# Adafruit_QT_Py_ESP32_Pico.net
KiCad netlist of a schematic drawn in EAGLE
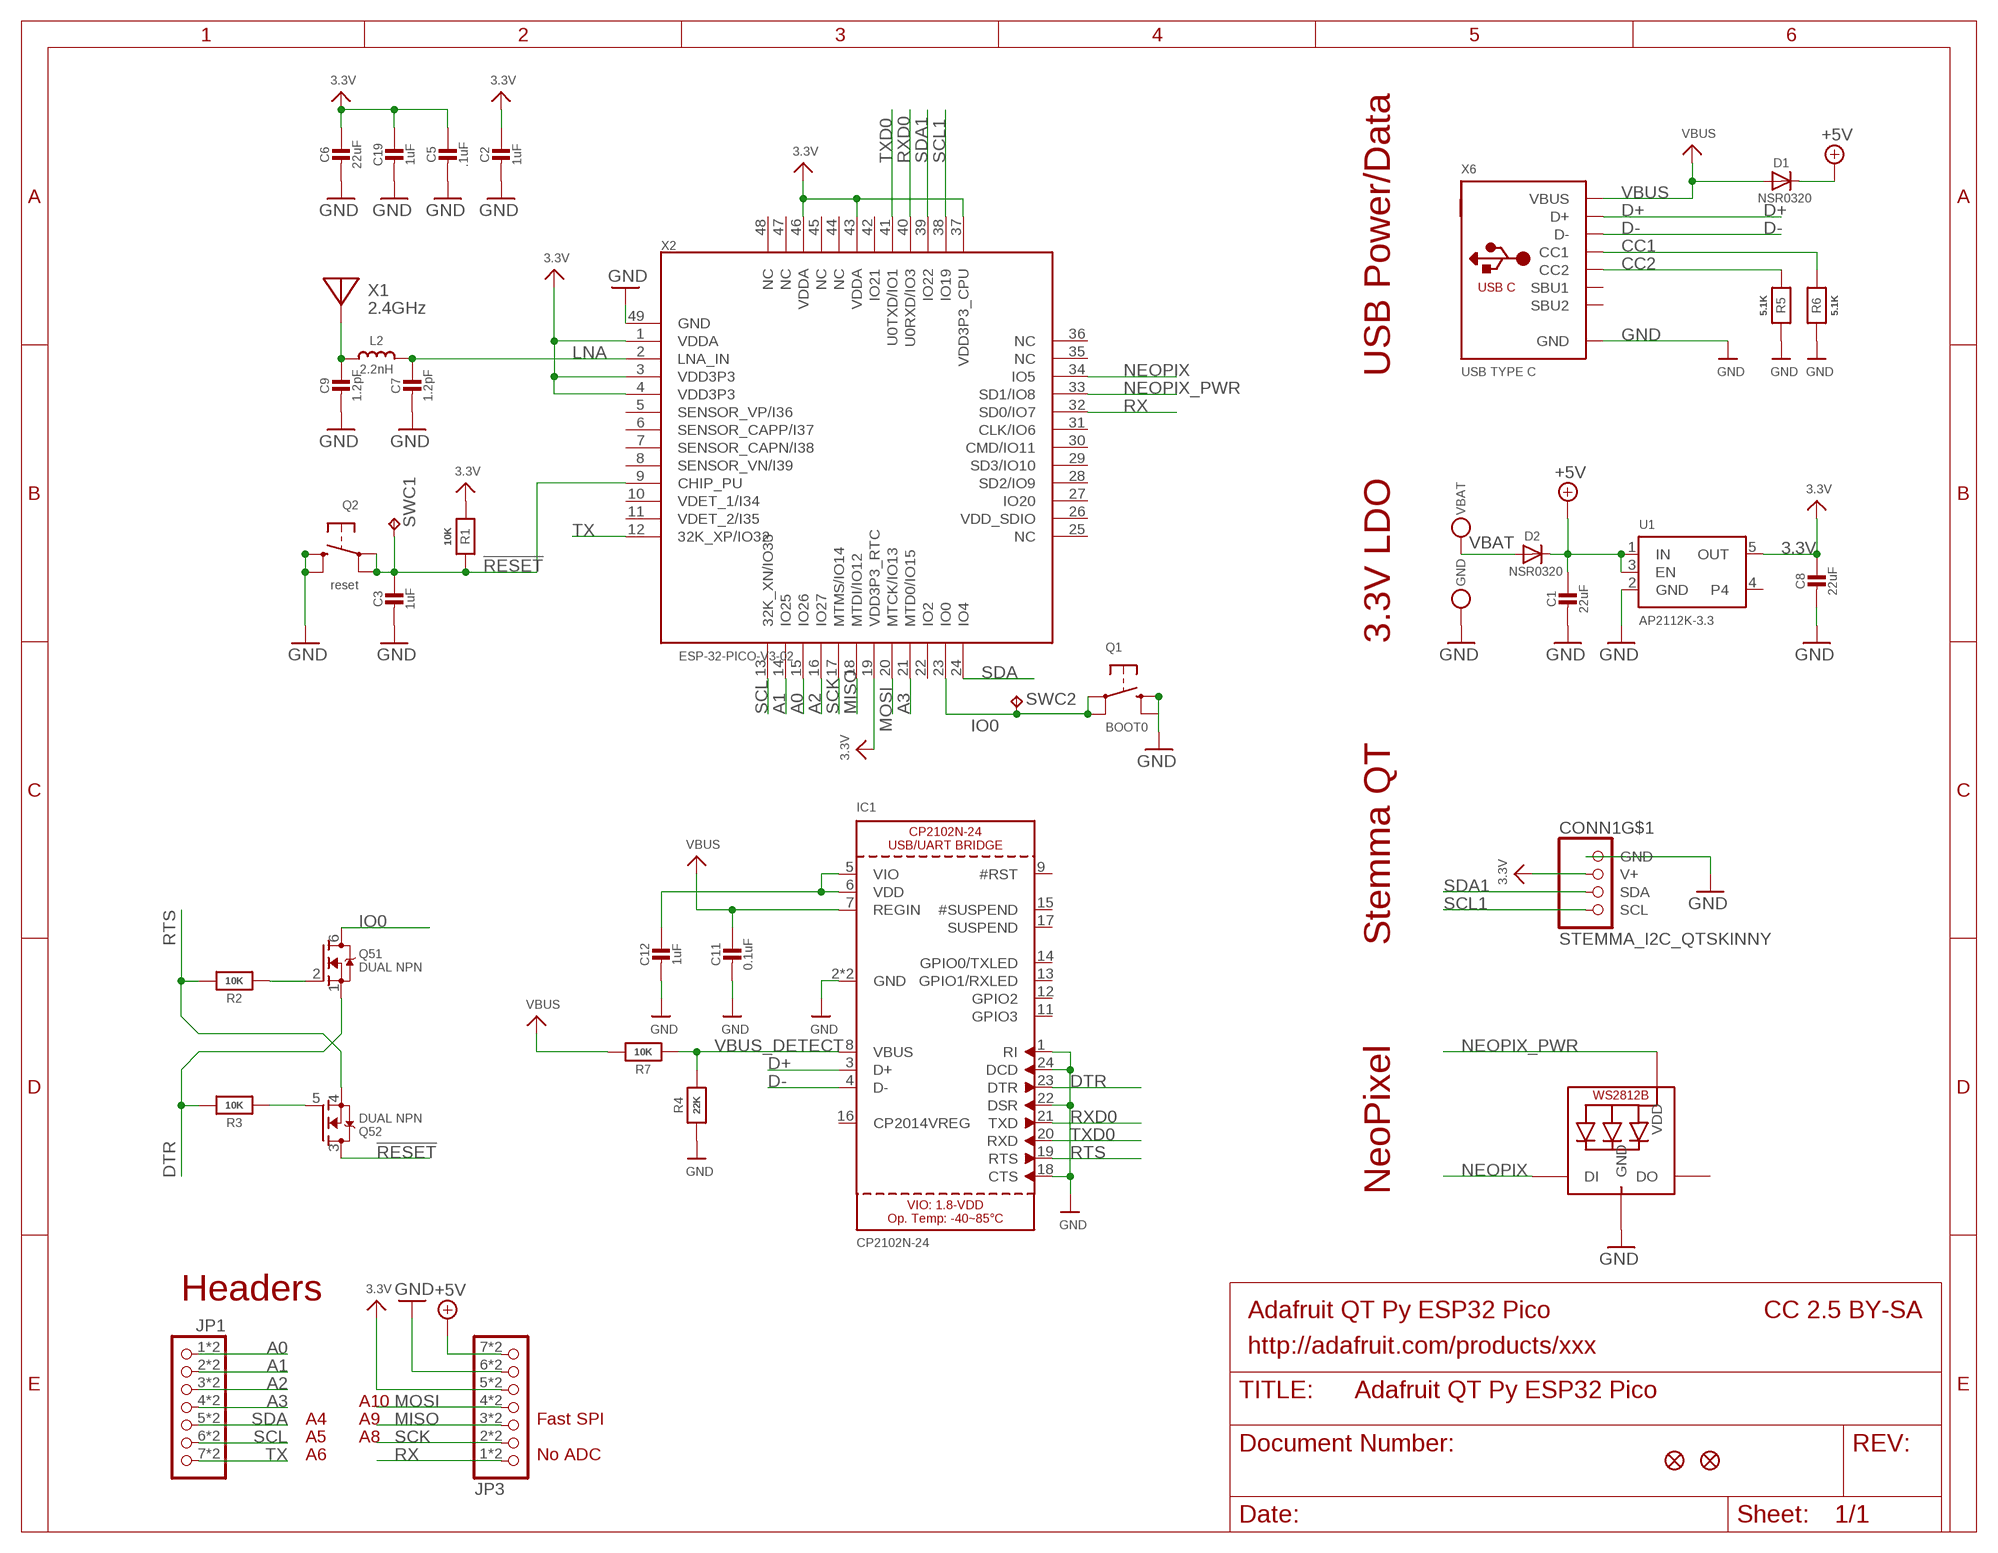
[diagram p0: schematic, sheet 1]

(export (version "E")
  (design (tool "Eeschema 10.0.6"))
  (components
    (comp (ref "C1")
      (value "22uF")
      (footprint "eagle-import:0805-NO")
      (libsource (lib "eagle-import") (part "CAP_CERAMIC0805-NOOUTLINE"))
    )
    (comp (ref "C2")
      (value "1uF")
      (footprint "eagle-import:_0402NO")
      (libsource (lib "eagle-import") (part "CAP_CERAMIC_0402NO"))
    )
    (comp (ref "C3")
      (value "1uF")
      (footprint "eagle-import:_0402NO")
      (libsource (lib "eagle-import") (part "CAP_CERAMIC_0402NO"))
    )
    (comp (ref "C5")
      (value ".1uF")
      (footprint "eagle-import:_0402NO")
      (libsource (lib "eagle-import") (part "CAP_CERAMIC_0402NO"))
    )
    (comp (ref "C6")
      (value "22uF")
      (footprint "eagle-import:0805-NO")
      (libsource (lib "eagle-import") (part "CAP_CERAMIC0805-NOOUTLINE"))
    )
    (comp (ref "C7")
      (value "1.2pF")
      (footprint "eagle-import:_0402NO")
      (libsource (lib "eagle-import") (part "CAP_CERAMIC_0402NO"))
    )
    (comp (ref "C8")
      (value "22uF")
      (footprint "eagle-import:0805-NO")
      (libsource (lib "eagle-import") (part "CAP_CERAMIC0805-NOOUTLINE"))
    )
    (comp (ref "C9")
      (value "1.2pF")
      (footprint "eagle-import:_0402NO")
      (libsource (lib "eagle-import") (part "CAP_CERAMIC_0402NO"))
    )
    (comp (ref "C11")
      (value "0.1uF")
      (footprint "eagle-import:_0402NO")
      (libsource (lib "eagle-import") (part "CAP_CERAMIC_0402NO"))
    )
    (comp (ref "C12")
      (value "1uF")
      (footprint "eagle-import:_0402NO")
      (libsource (lib "eagle-import") (part "CAP_CERAMIC_0402NO"))
    )
    (comp (ref "C19")
      (value "1uF")
      (footprint "eagle-import:0603-NO_WIDE")
      (libsource (lib "eagle-import") (part "CAP_CERAMIC_0603WIDE"))
    )
    (comp (ref "CONN1")
      (value "STEMMA_I2C_QTSKINNY")
      (footprint "eagle-import:JST_SH4_SKINNY")
      (libsource (lib "eagle-import") (part "STEMMA_I2C_QTSKINNY"))
    )
    (comp (ref "D1")
      (value "NSR0320")
      (footprint "eagle-import:SOD-323_MINI")
      (libsource (lib "eagle-import") (part "DIODE_SOD323MINI"))
    )
    (comp (ref "D2")
      (value "NSR0320")
      (footprint "eagle-import:SOD-323_MINI")
      (libsource (lib "eagle-import") (part "DIODE_SOD323MINI"))
    )
    (comp (ref "GND")
      (value "TESTPOINT_MINUS")
      (footprint "eagle-import:TESTPOINT_MINUS_1X3MM")
      (libsource (lib "eagle-import") (part "TESTPOINT_MINUS"))
    )
    (comp (ref "IC1")
      (value "CP2102N-24")
      (footprint "eagle-import:QFN24_4MM_SMSC")
      (libsource (lib "eagle-import") (part "CP2102N-24"))
    )
    (comp (ref "JP1")
      (value "HEADER-1X7_CASTEL")
      (footprint "eagle-import:1X07_CASTEL")
      (libsource (lib "eagle-import") (part "HEADER-1X7_CASTEL"))
    )
    (comp (ref "JP3")
      (value "HEADER-1X7_CASTEL")
      (footprint "eagle-import:1X07_CASTEL")
      (libsource (lib "eagle-import") (part "HEADER-1X7_CASTEL"))
    )
    (comp (ref "L2")
      (value "2.2nH")
      (footprint "eagle-import:_0402")
      (libsource (lib "eagle-import") (part "INDUCTOR_0402"))
    )
    (comp (ref "LED1")
      (value "WS2812B_SK6805_1515")
      (footprint "eagle-import:SK6805_1515")
      (libsource (lib "eagle-import") (part "WS2812B_SK6805_1515"))
    )
    (comp (ref "Q1")
      (value "BOOT0")
      (footprint "eagle-import:BTN_KMR2_4.6X2.8")
      (libsource (lib "eagle-import") (part "SWITCH_TACT_SMT4.6X2.8"))
    )
    (comp (ref "Q2")
      (value "reset")
      (footprint "eagle-import:BTN_KMR2_4.6X2.8")
      (libsource (lib "eagle-import") (part "SWITCH_TACT_SMT4.6X2.8"))
    )
    (comp (ref "Q5")
      (value "DUAL NPN")
      (footprint "eagle-import:SOT363")
      (libsource (lib "eagle-import") (part "MOSFET-N_DUAL"))
    )
    (comp (ref "R1")
      (value "10K")
      (footprint "eagle-import:_0402NO")
      (libsource (lib "eagle-import") (part "RESISTOR_0402NO"))
    )
    (comp (ref "R2")
      (value "10K")
      (footprint "eagle-import:_0402NO")
      (libsource (lib "eagle-import") (part "RESISTOR_0402NO"))
    )
    (comp (ref "R3")
      (value "10K")
      (footprint "eagle-import:_0402NO")
      (libsource (lib "eagle-import") (part "RESISTOR_0402NO"))
    )
    (comp (ref "R4")
      (value "22K")
      (footprint "eagle-import:_0402NO")
      (libsource (lib "eagle-import") (part "RESISTOR_0402NO"))
    )
    (comp (ref "R5")
      (value "5.1K")
      (footprint "eagle-import:_0402NO")
      (libsource (lib "eagle-import") (part "RESISTOR_0402NO"))
    )
    (comp (ref "R6")
      (value "5.1K")
      (footprint "eagle-import:_0402NO")
      (libsource (lib "eagle-import") (part "RESISTOR_0402NO"))
    )
    (comp (ref "R7")
      (value "10K")
      (footprint "eagle-import:_0402NO")
      (libsource (lib "eagle-import") (part "RESISTOR_0402NO"))
    )
    (comp (ref "SWC1")
      (value "TPB1,27")
      (footprint "eagle-import:B1,27")
      (libsource (lib "eagle-import") (part "TPB1,27"))
    )
    (comp (ref "SWC2")
      (value "TPB1,27")
      (footprint "eagle-import:B1,27")
      (libsource (lib "eagle-import") (part "TPB1,27"))
    )
    (comp (ref "U$6")
      (value "FIDUCIAL_1MM")
      (footprint "eagle-import:FIDUCIAL_1MM")
      (libsource (lib "eagle-import") (part "FIDUCIAL_1MM"))
    )
    (comp (ref "U$8")
      (value "FIDUCIAL_1MM")
      (footprint "eagle-import:FIDUCIAL_1MM")
      (libsource (lib "eagle-import") (part "FIDUCIAL_1MM"))
    )
    (comp (ref "U1")
      (value "AP2112K-3.3")
      (footprint "eagle-import:SOT23-5")
      (libsource (lib "eagle-import") (part "VREG_SOT23-5"))
    )
    (comp (ref "VBAT")
      (value "TESTPOINT_PLUS13")
      (footprint "eagle-import:TESTPOINT_PLUS_1X3MM")
      (libsource (lib "eagle-import") (part "TESTPOINT_PLUS13"))
    )
    (comp (ref "X1")
      (value "2.4GHz")
      (footprint "eagle-import:ANT_2450AT18B100")
      (libsource (lib "eagle-import") (part "ANTENNA_JOHANSON_2450AT18B100"))
    )
    (comp (ref "X2")
      (value "ESP-32-PICO-V3-02")
      (footprint "eagle-import:QFN48_7X7")
      (libsource (lib "eagle-import") (part "ESP-32-PICO-V3-02"))
    )
    (comp (ref "X6")
      (value "USB TYPE C")
      (footprint "eagle-import:USB_C_CUSB31-CFM2AX-01-X")
      (libsource (lib "eagle-import") (part "USB_C"))
    )
  )
  (nets
    (net (code "1") (name "+5V") (class "Default")
      (node (ref "C1") (pin "1") (pinfunction "1_1") (pintype "passive"))
      (node (ref "D1") (pin "C") (pinfunction "C_C") (pintype "passive"))
      (node (ref "D2") (pin "C") (pinfunction "C_C") (pintype "passive"))
      (node (ref "JP3") (pin "7") (pinfunction "7_7") (pintype "passive"))
      (node (ref "JP3") (pin "7C") (pinfunction "7_7C") (pintype "passive"))
      (node (ref "U1") (pin "1") (pinfunction "IN_1") (pintype "power_in"))
      (node (ref "U1") (pin "3") (pinfunction "EN_3") (pintype "input"))
    )
    (net (code "2") (name "/A0") (class "Default")
      (node (ref "JP1") (pin "1") (pinfunction "1_1") (pintype "passive"))
      (node (ref "JP1") (pin "1C") (pinfunction "1_1C") (pintype "passive"))
      (node (ref "X2") (pin "15") (pinfunction "IO26_15") (pintype "bidirectional"))
    )
    (net (code "3") (name "/A1") (class "Default")
      (node (ref "JP1") (pin "2") (pinfunction "2_2") (pintype "passive"))
      (node (ref "JP1") (pin "2C") (pinfunction "2_2C") (pintype "passive"))
      (node (ref "X2") (pin "14") (pinfunction "IO25_14") (pintype "bidirectional"))
    )
    (net (code "4") (name "/A2") (class "Default")
      (node (ref "JP1") (pin "3") (pinfunction "3_3") (pintype "passive"))
      (node (ref "JP1") (pin "3C") (pinfunction "3_3C") (pintype "passive"))
      (node (ref "X2") (pin "16") (pinfunction "IO27_16") (pintype "bidirectional"))
    )
    (net (code "5") (name "/A3") (class "Default")
      (node (ref "JP1") (pin "4") (pinfunction "4_4") (pintype "passive"))
      (node (ref "JP1") (pin "4C") (pinfunction "4_4C") (pintype "passive"))
      (node (ref "X2") (pin "21") (pinfunction "MTD0/IO15_21") (pintype "bidirectional"))
    )
    (net (code "6") (name "/CC1") (class "Default")
      (node (ref "R6") (pin "2") (pinfunction "2_2") (pintype "passive"))
      (node (ref "X6") (pin "A5") (pinfunction "CC1_A5") (pintype "bidirectional"))
    )
    (net (code "7") (name "/CC2") (class "Default")
      (node (ref "R5") (pin "2") (pinfunction "2_2") (pintype "passive"))
      (node (ref "X6") (pin "B5") (pinfunction "CC2_B5") (pintype "bidirectional"))
    )
    (net (code "8") (name "/D+") (class "Default")
      (node (ref "IC1") (pin "3") (pinfunction "D+_3") (pintype "bidirectional"))
      (node (ref "X6") (pin "A6") (pinfunction "D+_A6") (pintype "bidirectional"))
      (node (ref "X6") (pin "B6") (pinfunction "D+_B6") (pintype "bidirectional"))
    )
    (net (code "9") (name "/D-") (class "Default")
      (node (ref "IC1") (pin "4") (pinfunction "D-_4") (pintype "bidirectional"))
      (node (ref "X6") (pin "A7") (pinfunction "D-_A7") (pintype "bidirectional"))
      (node (ref "X6") (pin "B7") (pinfunction "D-_B7") (pintype "bidirectional"))
    )
    (net (code "10") (name "/DTR") (class "Default")
      (node (ref "IC1") (pin "23") (pinfunction "DTR_23") (pintype "output"))
      (node (ref "Q5") (pin "1") (pinfunction "S_1") (pintype "bidirectional"))
      (node (ref "R3") (pin "2") (pinfunction "2_2") (pintype "passive"))
    )
    (net (code "11") (name "/IO0") (class "Default")
      (node (ref "Q1") (pin "A") (pinfunction "P_A") (pintype "passive"))
      (node (ref "Q1") (pin "A'") (pinfunction "P1_A'") (pintype "passive"))
      (node (ref "Q5") (pin "6") (pinfunction "D_6") (pintype "bidirectional"))
      (node (ref "SWC2") (pin "TP") (pinfunction "TP_TP") (pintype "input"))
      (node (ref "X2") (pin "23") (pinfunction "IO0_23") (pintype "bidirectional"))
    )
    (net (code "12") (name "/LNA") (class "Default")
      (node (ref "C7") (pin "1") (pinfunction "1_1") (pintype "passive"))
      (node (ref "L2") (pin "2") (pinfunction "2_2") (pintype "passive"))
      (node (ref "X2") (pin "2") (pinfunction "LNA_IN_2") (pintype "bidirectional"))
    )
    (net (code "13") (name "/MISO") (class "Default")
      (node (ref "JP3") (pin "3") (pinfunction "3_3") (pintype "passive"))
      (node (ref "JP3") (pin "3C") (pinfunction "3_3C") (pintype "passive"))
      (node (ref "X2") (pin "18") (pinfunction "MTDI/IO12_18") (pintype "bidirectional"))
    )
    (net (code "14") (name "/MOSI") (class "Default")
      (node (ref "JP3") (pin "4") (pinfunction "4_4") (pintype "passive"))
      (node (ref "JP3") (pin "4C") (pinfunction "4_4C") (pintype "passive"))
      (node (ref "X2") (pin "20") (pinfunction "MTCK/IO13_20") (pintype "bidirectional"))
    )
    (net (code "15") (name "/NEOPIX") (class "Default")
      (node (ref "LED1") (pin "1") (pinfunction "DI_1") (pintype "input"))
      (node (ref "X2") (pin "34") (pinfunction "IO5_34") (pintype "bidirectional"))
    )
    (net (code "16") (name "/NEOPIX_PWR") (class "Default")
      (node (ref "LED1") (pin "2") (pinfunction "VDD_2") (pintype "power_in"))
      (node (ref "X2") (pin "33") (pinfunction "SD1/IO8_33") (pintype "bidirectional"))
    )
    (net (code "17") (name "/RTS") (class "Default")
      (node (ref "IC1") (pin "19") (pinfunction "RTS_19") (pintype "output"))
      (node (ref "Q5") (pin "4") (pinfunction "S_4") (pintype "bidirectional"))
      (node (ref "R2") (pin "2") (pinfunction "2_2") (pintype "passive"))
    )
    (net (code "18") (name "/RX") (class "Default")
      (node (ref "JP3") (pin "1") (pinfunction "1_1") (pintype "passive"))
      (node (ref "JP3") (pin "1C") (pinfunction "1_1C") (pintype "passive"))
      (node (ref "X2") (pin "32") (pinfunction "SD0/IO7_32") (pintype "bidirectional"))
    )
    (net (code "19") (name "/RXD0") (class "Default")
      (node (ref "IC1") (pin "21") (pinfunction "TXD_21") (pintype "output"))
      (node (ref "X2") (pin "40") (pinfunction "U0RXD/IO3_40") (pintype "bidirectional"))
    )
    (net (code "20") (name "/SCK") (class "Default")
      (node (ref "JP3") (pin "2") (pinfunction "2_2") (pintype "passive"))
      (node (ref "JP3") (pin "2C") (pinfunction "2_2C") (pintype "passive"))
      (node (ref "X2") (pin "17") (pinfunction "MTMS/IO14_17") (pintype "bidirectional"))
    )
    (net (code "21") (name "/SCL") (class "Default")
      (node (ref "JP1") (pin "6") (pinfunction "6_6") (pintype "passive"))
      (node (ref "JP1") (pin "6C") (pinfunction "6_6C") (pintype "passive"))
      (node (ref "X2") (pin "13") (pinfunction "32K_XN/IO33_13") (pintype "bidirectional"))
    )
    (net (code "22") (name "/SCL1") (class "Default")
      (node (ref "CONN1") (pin "4") (pinfunction "SCL_4") (pintype "passive"))
      (node (ref "X2") (pin "38") (pinfunction "IO19_38") (pintype "bidirectional"))
    )
    (net (code "23") (name "/SDA") (class "Default")
      (node (ref "JP1") (pin "5") (pinfunction "5_5") (pintype "passive"))
      (node (ref "JP1") (pin "5C") (pinfunction "5_5C") (pintype "passive"))
      (node (ref "X2") (pin "24") (pinfunction "IO4_24") (pintype "bidirectional"))
    )
    (net (code "24") (name "/SDA1") (class "Default")
      (node (ref "CONN1") (pin "3") (pinfunction "SDA_3") (pintype "passive"))
      (node (ref "X2") (pin "39") (pinfunction "IO22_39") (pintype "bidirectional"))
    )
    (net (code "25") (name "/TX") (class "Default")
      (node (ref "JP1") (pin "7") (pinfunction "7_7") (pintype "passive"))
      (node (ref "JP1") (pin "7C") (pinfunction "7_7C") (pintype "passive"))
      (node (ref "X2") (pin "12") (pinfunction "32K_XP/IO32_12") (pintype "bidirectional"))
    )
    (net (code "26") (name "/TXD0") (class "Default")
      (node (ref "IC1") (pin "20") (pinfunction "RXD_20") (pintype "input"))
      (node (ref "X2") (pin "41") (pinfunction "U0TXD/IO1_41") (pintype "bidirectional"))
    )
    (net (code "27") (name "/VBAT") (class "Default")
      (node (ref "D2") (pin "A") (pinfunction "A_A") (pintype "passive"))
      (node (ref "VBAT") (pin "P$1") (pinfunction "P$1_P$1") (pintype "bidirectional"))
    )
    (net (code "28") (name "/VBUS_DETECT") (class "Default")
      (node (ref "IC1") (pin "8") (pinfunction "VBUS_8") (pintype "power_in"))
      (node (ref "R4") (pin "2") (pinfunction "2_2") (pintype "passive"))
      (node (ref "R7") (pin "1") (pinfunction "1_1") (pintype "passive"))
    )
    (net (code "29") (name "/~{RESET}") (class "Default")
      (node (ref "C3") (pin "1") (pinfunction "1_1") (pintype "passive"))
      (node (ref "Q2") (pin "A") (pinfunction "P_A") (pintype "passive"))
      (node (ref "Q2") (pin "A'") (pinfunction "P1_A'") (pintype "passive"))
      (node (ref "Q5") (pin "3") (pinfunction "D_3") (pintype "bidirectional"))
      (node (ref "R1") (pin "2") (pinfunction "2_2") (pintype "passive"))
      (node (ref "SWC1") (pin "TP") (pinfunction "TP_TP") (pintype "input"))
      (node (ref "X2") (pin "9") (pinfunction "CHIP_PU_9") (pintype "input"))
    )
    (net (code "30") (name "3.3V") (class "Default")
      (node (ref "C19") (pin "1") (pinfunction "1_1") (pintype "passive"))
      (node (ref "C2") (pin "1") (pinfunction "1_1") (pintype "passive"))
      (node (ref "C5") (pin "1") (pinfunction "1_1") (pintype "passive"))
      (node (ref "C6") (pin "1") (pinfunction "1_1") (pintype "passive"))
      (node (ref "C8") (pin "1") (pinfunction "1_1") (pintype "passive"))
      (node (ref "CONN1") (pin "2") (pinfunction "V+_2") (pintype "passive"))
      (node (ref "JP3") (pin "5") (pinfunction "5_5") (pintype "passive"))
      (node (ref "JP3") (pin "5C") (pinfunction "5_5C") (pintype "passive"))
      (node (ref "R1") (pin "1") (pinfunction "1_1") (pintype "passive"))
      (node (ref "U1") (pin "5") (pinfunction "OUT_5") (pintype "power_in"))
      (node (ref "X2") (pin "1") (pinfunction "VDDA_1") (pintype "power_in"))
      (node (ref "X2") (pin "19") (pinfunction "VDD3P3_RTC_19") (pintype "power_in"))
      (node (ref "X2") (pin "3") (pinfunction "VDD3P3_3") (pintype "power_in"))
      (node (ref "X2") (pin "37") (pinfunction "VDD3P3_CPU_37") (pintype "power_in"))
      (node (ref "X2") (pin "4") (pinfunction "VDD3P3_4") (pintype "power_in"))
      (node (ref "X2") (pin "43") (pinfunction "VDDA_43") (pintype "power_in"))
      (node (ref "X2") (pin "46") (pinfunction "VDDA_46") (pintype "power_in"))
    )
    (net (code "31") (name "GND") (class "Default")
      (node (ref "C1") (pin "2") (pinfunction "2_2") (pintype "passive"))
      (node (ref "C11") (pin "2") (pinfunction "2_2") (pintype "passive"))
      (node (ref "C12") (pin "2") (pinfunction "2_2") (pintype "passive"))
      (node (ref "C19") (pin "2") (pinfunction "2_2") (pintype "passive"))
      (node (ref "C2") (pin "2") (pinfunction "2_2") (pintype "passive"))
      (node (ref "C3") (pin "2") (pinfunction "2_2") (pintype "passive"))
      (node (ref "C5") (pin "2") (pinfunction "2_2") (pintype "passive"))
      (node (ref "C6") (pin "2") (pinfunction "2_2") (pintype "passive"))
      (node (ref "C7") (pin "2") (pinfunction "2_2") (pintype "passive"))
      (node (ref "C8") (pin "2") (pinfunction "2_2") (pintype "passive"))
      (node (ref "C9") (pin "2") (pinfunction "2_2") (pintype "passive"))
      (node (ref "CONN1") (pin "1") (pinfunction "GND_1") (pintype "passive"))
      (node (ref "GND") (pin "P$1") (pinfunction "P$1_P$1") (pintype "bidirectional"))
      (node (ref "IC1") (pin "1") (pinfunction "RI_1") (pintype "input"))
      (node (ref "IC1") (pin "18") (pinfunction "CTS_18") (pintype "input"))
      (node (ref "IC1") (pin "2") (pinfunction "GND_2") (pintype "power_in"))
      (node (ref "IC1") (pin "22") (pinfunction "DSR_22") (pintype "input"))
      (node (ref "IC1") (pin "24") (pinfunction "DCD_24") (pintype "input"))
      (node (ref "IC1") (pin "THERM") (pinfunction "GND_THERM") (pintype "power_in"))
      (node (ref "JP3") (pin "6") (pinfunction "6_6") (pintype "passive"))
      (node (ref "JP3") (pin "6C") (pinfunction "6_6C") (pintype "passive"))
      (node (ref "LED1") (pin "4") (pinfunction "GND_4") (pintype "power_in"))
      (node (ref "Q1") (pin "B") (pinfunction "S_B") (pintype "passive"))
      (node (ref "Q1") (pin "B'") (pinfunction "S1_B'") (pintype "passive"))
      (node (ref "Q2") (pin "B") (pinfunction "S_B") (pintype "passive"))
      (node (ref "Q2") (pin "B'") (pinfunction "S1_B'") (pintype "passive"))
      (node (ref "R4") (pin "1") (pinfunction "1_1") (pintype "passive"))
      (node (ref "R5") (pin "1") (pinfunction "1_1") (pintype "passive"))
      (node (ref "R6") (pin "1") (pinfunction "1_1") (pintype "passive"))
      (node (ref "U1") (pin "2") (pinfunction "GND_2") (pintype "power_in"))
      (node (ref "X2") (pin "49") (pinfunction "GND_49") (pintype "power_in"))
      (node (ref "X6") (pin "A1B12") (pinfunction "GND_A1B12") (pintype "power_in"))
      (node (ref "X6") (pin "B1A12") (pinfunction "GND_B1A12") (pintype "power_in"))
    )
    (net (code "32") (name "Net-(IC1-VDD)") (class "Default")
      (node (ref "C12") (pin "1") (pinfunction "1_1") (pintype "passive"))
      (node (ref "IC1") (pin "5") (pinfunction "VIO_5") (pintype "power_in"))
      (node (ref "IC1") (pin "6") (pinfunction "VDD_6") (pintype "power_in"))
    )
    (net (code "33") (name "Net-(Q5A-G)") (class "Default")
      (node (ref "Q5") (pin "2") (pinfunction "G_2") (pintype "bidirectional"))
      (node (ref "R2") (pin "1") (pinfunction "1_1") (pintype "passive"))
    )
    (net (code "34") (name "Net-(Q5B-G)") (class "Default")
      (node (ref "Q5") (pin "5") (pinfunction "G_5") (pintype "bidirectional"))
      (node (ref "R3") (pin "1") (pinfunction "1_1") (pintype "passive"))
    )
    (net (code "35") (name "Net-(X1-P$1)") (class "Default")
      (node (ref "C9") (pin "1") (pinfunction "1_1") (pintype "passive"))
      (node (ref "L2") (pin "1") (pinfunction "1_1") (pintype "passive"))
      (node (ref "X1") (pin "FP") (pinfunction "P$1_FP") (pintype "passive"))
    )
    (net (code "36") (name "VBUS") (class "Default")
      (node (ref "C11") (pin "1") (pinfunction "1_1") (pintype "passive"))
      (node (ref "D1") (pin "A") (pinfunction "A_A") (pintype "passive"))
      (node (ref "IC1") (pin "7") (pinfunction "REGIN_7") (pintype "power_in"))
      (node (ref "R7") (pin "2") (pinfunction "2_2") (pintype "passive"))
      (node (ref "X6") (pin "A4B9") (pinfunction "VBUS_A4B9") (pintype "power_in"))
      (node (ref "X6") (pin "B4A9") (pinfunction "VBUS_B4A9") (pintype "power_in"))
    )
    (net (code "37") (name "unconnected-(IC1-#RST-Pad9)") (class "Default")
      (node (ref "IC1") (pin "9") (pinfunction "#RST_9") (pintype "bidirectional"))
    )
    (net (code "38") (name "unconnected-(IC1-#SUSPEND-Pad15)") (class "Default")
      (node (ref "IC1") (pin "15") (pinfunction "#SUSPEND_15") (pintype "output"))
    )
    (net (code "39") (name "unconnected-(IC1-CP2014VREG-Pad16)") (class "Default")
      (node (ref "IC1") (pin "16") (pinfunction "CP2014VREG_16") (pintype "passive"))
    )
    (net (code "40") (name "unconnected-(IC1-GPIO0{slash}TXLED-Pad14)") (class "Default")
      (node (ref "IC1") (pin "14") (pinfunction "GPIO0/TXLED_14") (pintype "bidirectional"))
    )
    (net (code "41") (name "unconnected-(IC1-GPIO1{slash}RXLED-Pad13)") (class "Default")
      (node (ref "IC1") (pin "13") (pinfunction "GPIO1/RXLED_13") (pintype "bidirectional"))
    )
    (net (code "42") (name "unconnected-(IC1-GPIO2-Pad12)") (class "Default")
      (node (ref "IC1") (pin "12") (pinfunction "GPIO2_12") (pintype "bidirectional"))
    )
    (net (code "43") (name "unconnected-(IC1-GPIO3-Pad11)") (class "Default")
      (node (ref "IC1") (pin "11") (pinfunction "GPIO3_11") (pintype "bidirectional"))
    )
    (net (code "44") (name "unconnected-(IC1-SUSPEND-Pad17)") (class "Default")
      (node (ref "IC1") (pin "17") (pinfunction "SUSPEND_17") (pintype "output"))
    )
    (net (code "45") (name "unconnected-(LED1-DO-Pad3)") (class "Default")
      (node (ref "LED1") (pin "3") (pinfunction "DO_3") (pintype "output"))
    )
    (net (code "46") (name "unconnected-(U1-P4-Pad4)") (class "Default")
      (node (ref "U1") (pin "4") (pinfunction "P4_4") (pintype "bidirectional"))
    )
    (net (code "47") (name "unconnected-(X2-CLK{slash}IO6-Pad31)") (class "Default")
      (node (ref "X2") (pin "31") (pinfunction "CLK/IO6_31") (pintype "no_connect"))
    )
    (net (code "48") (name "unconnected-(X2-CMD{slash}IO11-Pad30)") (class "Default")
      (node (ref "X2") (pin "30") (pinfunction "CMD/IO11_30") (pintype "no_connect"))
    )
    (net (code "49") (name "unconnected-(X2-IO2-Pad22)") (class "Default")
      (node (ref "X2") (pin "22") (pinfunction "IO2_22") (pintype "bidirectional"))
    )
    (net (code "50") (name "unconnected-(X2-IO20-Pad27)") (class "Default")
      (node (ref "X2") (pin "27") (pinfunction "IO20_27") (pintype "bidirectional"))
    )
    (net (code "51") (name "unconnected-(X2-IO21-Pad42)") (class "Default")
      (node (ref "X2") (pin "42") (pinfunction "IO21_42") (pintype "bidirectional"))
    )
    (net (code "52") (name "unconnected-(X2-NC-Pad25)") (class "Default")
      (node (ref "X2") (pin "25") (pinfunction "NC_25") (pintype "no_connect"))
    )
    (net (code "53") (name "unconnected-(X2-NC-Pad35)") (class "Default")
      (node (ref "X2") (pin "35") (pinfunction "NC_35") (pintype "no_connect"))
    )
    (net (code "54") (name "unconnected-(X2-NC-Pad36)") (class "Default")
      (node (ref "X2") (pin "36") (pinfunction "NC_36") (pintype "no_connect"))
    )
    (net (code "55") (name "unconnected-(X2-NC-Pad44)") (class "Default")
      (node (ref "X2") (pin "44") (pinfunction "NC_44") (pintype "no_connect"))
    )
    (net (code "56") (name "unconnected-(X2-NC-Pad45)") (class "Default")
      (node (ref "X2") (pin "45") (pinfunction "NC_45") (pintype "no_connect"))
    )
    (net (code "57") (name "unconnected-(X2-NC-Pad47)") (class "Default")
      (node (ref "X2") (pin "47") (pinfunction "NC_47") (pintype "no_connect"))
    )
    (net (code "58") (name "unconnected-(X2-NC-Pad48)") (class "Default")
      (node (ref "X2") (pin "48") (pinfunction "NC_48") (pintype "no_connect"))
    )
    (net (code "59") (name "unconnected-(X2-SD2{slash}IO9-Pad28)") (class "Default")
      (node (ref "X2") (pin "28") (pinfunction "SD2/IO9_28") (pintype "no_connect"))
    )
    (net (code "60") (name "unconnected-(X2-SD3{slash}IO10-Pad29)") (class "Default")
      (node (ref "X2") (pin "29") (pinfunction "SD3/IO10_29") (pintype "no_connect"))
    )
    (net (code "61") (name "unconnected-(X2-SENSOR_CAPN{slash}I38-Pad7)") (class "Default")
      (node (ref "X2") (pin "7") (pinfunction "SENSOR_CAPN/I38_7") (pintype "input"))
    )
    (net (code "62") (name "unconnected-(X2-SENSOR_CAPP{slash}I37-Pad6)") (class "Default")
      (node (ref "X2") (pin "6") (pinfunction "SENSOR_CAPP/I37_6") (pintype "input"))
    )
    (net (code "63") (name "unconnected-(X2-SENSOR_VN{slash}I39-Pad8)") (class "Default")
      (node (ref "X2") (pin "8") (pinfunction "SENSOR_VN/I39_8") (pintype "input"))
    )
    (net (code "64") (name "unconnected-(X2-SENSOR_VP{slash}I36-Pad5)") (class "Default")
      (node (ref "X2") (pin "5") (pinfunction "SENSOR_VP/I36_5") (pintype "input"))
    )
    (net (code "65") (name "unconnected-(X2-VDD_SDIO-Pad26)") (class "Default")
      (node (ref "X2") (pin "26") (pinfunction "VDD_SDIO_26") (pintype "no_connect"))
    )
    (net (code "66") (name "unconnected-(X2-VDET_1{slash}I34-Pad10)") (class "Default")
      (node (ref "X2") (pin "10") (pinfunction "VDET_1/I34_10") (pintype "input"))
    )
    (net (code "67") (name "unconnected-(X2-VDET_2{slash}I35-Pad11)") (class "Default")
      (node (ref "X2") (pin "11") (pinfunction "VDET_2/I35_11") (pintype "input"))
    )
    (net (code "68") (name "unconnected-(X6-SBU1-PadA8)") (class "Default")
      (node (ref "X6") (pin "A8") (pinfunction "SBU1_A8") (pintype "bidirectional"))
    )
    (net (code "69") (name "unconnected-(X6-SBU2-PadB8)") (class "Default")
      (node (ref "X6") (pin "B8") (pinfunction "SBU2_B8") (pintype "bidirectional"))
    )
  )
)
